# STB_ControlBoard.net
KiCad netlist of a schematic drawn in Altium Designer
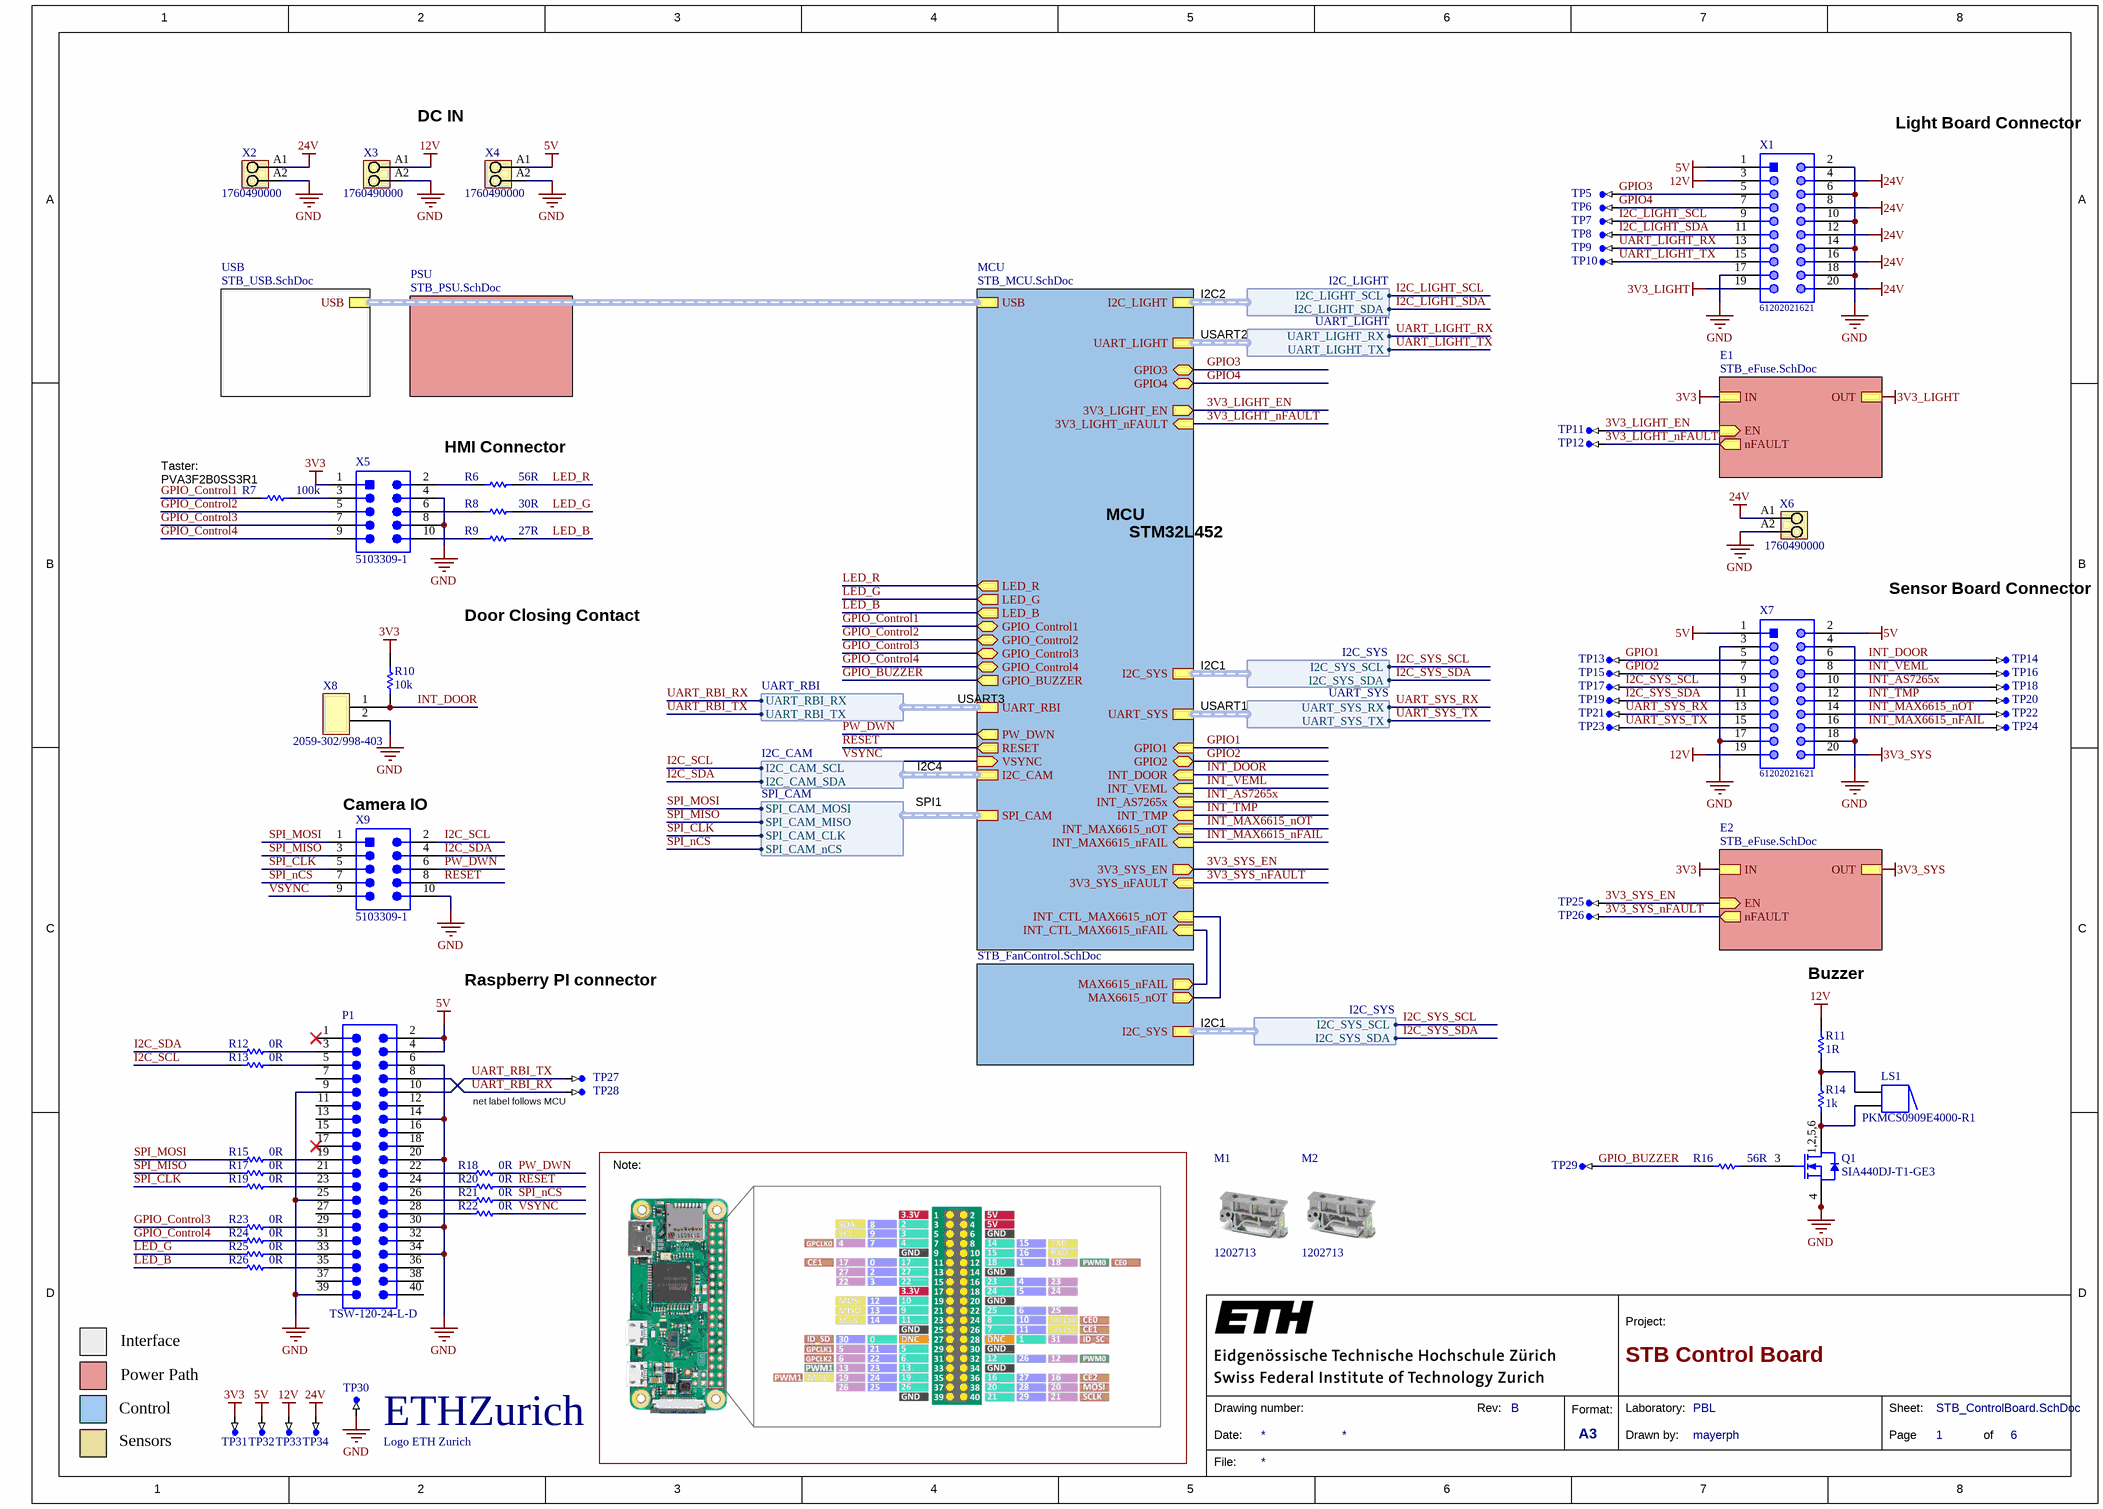
[diagram p0: STB_ControlBoard.SchDoc]

(export (version "E")
  (design (tool "Eeschema 10.0.6"))
  (components
    (comp (ref "A1")
      (value "Logo ETH Zurich")
      (footprint "eth-zurich_3mm")
      (libsource (lib "ETHZ Vault") (part "Logo ETH Zurich"))
    )
    (comp (ref "LS1")
      (value "PKMCS0909E4000-R1")
      (footprint "MURA- PKMCS0909E4000-2_V")
      (description "Audio Indicators & Alerts Piezo Buzzer, 12.5 V, -40 to 85 degC, 2-Pin SMD, RoHS, Tape and Reel")
      (fields (field (name "MANUFACTURER") "Murata"))
      (libsource (lib "Altium Content Vault") (part "MURA-PKMCS0909E4000-2"))
    )
    (comp (ref "M1")
      (value "1202713")
      (footprint "1202713")
      (description "EMI/EMD/EMC Protections")
      (fields (field (name "MANUFACTURER") "Phoenix Contact"))
      (libsource (lib "STB_Schlib") (part "1202713"))
    )
    (comp (ref "M2")
      (value "1202713")
      (footprint "1202713")
      (description "EMI/EMD/EMC Protections")
      (fields (field (name "MANUFACTURER") "Phoenix Contact"))
      (libsource (lib "STB_Schlib") (part "1202713"))
    )
    (comp (ref "P1")
      (value "TSW-120-24-L-D")
      (footprint "SMTC-TSW-120-24-X-D")
      (description "0.025\" SQ Post Header, Through-hole, Vertical, -55 to 125 degC, 2.54 mm Pitch, 40-Pin, Male, RoHS")
      (fields (field (name "MANUFACTURER") "Samtec"))
      (libsource (lib "Altium Content Vault") (part "SMTC-TSW-120-X-X-D-X"))
    )
    (comp (ref "Q1")
      (value "SIA440DJ-T1-GE3")
      (footprint "SC70-6L_65P210X80_HS-7L")
      (description "VISHAY   SIA440DJ-T1-GE3   MOSFET Transistor, N Channel, 12 A, 40 V, 0.021 ohm, 10 V")
      (fields (field (name "MANUFACTURER") "Vishay Siliconix"))
      (libsource (lib "STB_Schlib") (part "SIA440DJ-T1-GE3"))
    )
    (comp (ref "R6")
      (value "56R")
      (footprint "RESC1609X50X30LL10T20")
      (fields
        (field (name "MANUFACTURER") "Vishay Dale")
        (field (name "PART NUMBER") "CRCW060356R0FKEA")
        (field (name "TOLERANCE") "1%")
      )
      (libsource (lib "Altium Content Vault") (part "RES"))
    )
    (comp (ref "R7")
      (value "100k")
      (footprint "RESC1005X40X25LL05T10")
      (fields
        (field (name "PART NUMBER") "RC0402FR-07100KL")
        (field (name "MANUFACTURER") "Yageo / Phycomp")
        (field (name "TOLERANCE") "1%")
      )
      (libsource (lib "Altium Content Vault") (part "RES"))
    )
    (comp (ref "R8")
      (value "30R")
      (footprint "RESC1609X50X30LL10T20")
      (fields
        (field (name "PART NUMBER") "CRCW060330R0FKEA")
        (field (name "MANUFACTURER") "Vishay Dale")
        (field (name "TOLERANCE") "1%")
      )
      (libsource (lib "Altium Content Vault") (part "RES"))
    )
    (comp (ref "R9")
      (value "27R")
      (footprint "RESC1608X55X30LL15T15")
      (fields
        (field (name "PART NUMBER") "ERJ-3GEYJ270V")
        (field (name "MANUFACTURER") "Panasonic")
        (field (name "MANUFACTURER PART NUMBER") "ERJ-3EKF27R0V")
      )
      (libsource (lib "Altium Content Vault") (part "RES"))
    )
    (comp (ref "R10")
      (value "10k")
      (footprint "RESC1005X40X25LL05T05")
      (description "Chip Resistor, 10 KOhm, +/- 1%, 0.1 W, -55 to 155 degC, 0402 (1005 Metric), RoHS, Tape and Reel")
      (fields (field (name "TOLERANCE") "1%") (field (name "MANUFACTURER") "Panasonic"))
      (libsource (lib "Altium Content Vault") (part "RES-2"))
    )
    (comp (ref "R11")
      (value "1R")
      (footprint "RESC3225X70X50NL20T20")
      (fields
        (field (name "PART NUMBER") "ERJ14BQF1R0U")
        (field (name "MANUFACTURER") "Panasonic")
        (field (name "TOLERANCE") "1%")
      )
      (libsource (lib "Altium Content Vault") (part "RES"))
    )
    (comp (ref "R12")
      (value "0R")
      (footprint "RESC1005X40X25LL05T10")
      (fields (field (name "MANUFACTURER") "Yageo / Phycomp") (field (name "PART NUMBER") "RC0402JR-070RL"))
      (libsource (lib "Altium Content Vault") (part "RES"))
    )
    (comp (ref "R13")
      (value "0R")
      (footprint "RESC1005X40X25LL05T10")
      (fields (field (name "MANUFACTURER") "Yageo / Phycomp") (field (name "PART NUMBER") "RC0402JR-070RL"))
      (libsource (lib "Altium Content Vault") (part "RES"))
    )
    (comp (ref "R14")
      (value "1k")
      (footprint "RESC3216X70X50LL05T20")
      (fields
        (field (name "MANUFACTURER") "Panasonic")
        (field (name "PART NUMBER") "ERJ-8ENF1001V")
        (field (name "TOLERANCE") "1%")
      )
      (libsource (lib "Altium Content Vault") (part "RES"))
    )
    (comp (ref "R15")
      (value "0R")
      (footprint "RESC1005X40X25LL05T10")
      (fields (field (name "MANUFACTURER") "Yageo / Phycomp") (field (name "PART NUMBER") "RC0402JR-070RL"))
      (libsource (lib "Altium Content Vault") (part "RES"))
    )
    (comp (ref "R16")
      (value "56R")
      (footprint "RESC1609X50X30LL10T20")
      (fields
        (field (name "MANUFACTURER") "Vishay Dale")
        (field (name "PART NUMBER") "CRCW060356R0FKEA")
        (field (name "TOLERANCE") "1%")
      )
      (libsource (lib "Altium Content Vault") (part "RES"))
    )
    (comp (ref "R17")
      (value "0R")
      (footprint "RESC1005X40X25LL05T10")
      (fields (field (name "MANUFACTURER") "Yageo / Phycomp") (field (name "PART NUMBER") "RC0402JR-070RL"))
      (libsource (lib "Altium Content Vault") (part "RES"))
    )
    (comp (ref "R18")
      (value "0R")
      (footprint "RESC1005X40X25LL05T10")
      (fields (field (name "MANUFACTURER") "Yageo / Phycomp") (field (name "PART NUMBER") "RC0402JR-070RL"))
      (libsource (lib "Altium Content Vault") (part "RES"))
    )
    (comp (ref "R19")
      (value "0R")
      (footprint "RESC1005X40X25LL05T10")
      (fields (field (name "MANUFACTURER") "Yageo / Phycomp") (field (name "PART NUMBER") "RC0402JR-070RL"))
      (libsource (lib "Altium Content Vault") (part "RES"))
    )
    (comp (ref "R20")
      (value "0R")
      (footprint "RESC1005X40X25LL05T10")
      (fields (field (name "MANUFACTURER") "Yageo / Phycomp") (field (name "PART NUMBER") "RC0402JR-070RL"))
      (libsource (lib "Altium Content Vault") (part "RES"))
    )
    (comp (ref "R21")
      (value "0R")
      (footprint "RESC1005X40X25LL05T10")
      (fields (field (name "MANUFACTURER") "Yageo / Phycomp") (field (name "PART NUMBER") "RC0402JR-070RL"))
      (libsource (lib "Altium Content Vault") (part "RES"))
    )
    (comp (ref "R22")
      (value "0R")
      (footprint "RESC1005X40X25LL05T10")
      (fields (field (name "MANUFACTURER") "Yageo / Phycomp") (field (name "PART NUMBER") "RC0402JR-070RL"))
      (libsource (lib "Altium Content Vault") (part "RES"))
    )
    (comp (ref "R23")
      (value "0R")
      (footprint "RESC1005X40X25LL05T10")
      (fields (field (name "MANUFACTURER") "Yageo / Phycomp") (field (name "PART NUMBER") "RC0402JR-070RL"))
      (libsource (lib "Altium Content Vault") (part "RES"))
    )
    (comp (ref "R24")
      (value "0R")
      (footprint "RESC1005X40X25LL05T10")
      (fields (field (name "MANUFACTURER") "Yageo / Phycomp") (field (name "PART NUMBER") "RC0402JR-070RL"))
      (libsource (lib "Altium Content Vault") (part "RES"))
    )
    (comp (ref "R25")
      (value "0R")
      (footprint "RESC1005X40X25LL05T10")
      (fields (field (name "MANUFACTURER") "Yageo / Phycomp") (field (name "PART NUMBER") "RC0402JR-070RL"))
      (libsource (lib "Altium Content Vault") (part "RES"))
    )
    (comp (ref "R26")
      (value "0R")
      (footprint "RESC1005X40X25LL05T10")
      (fields (field (name "MANUFACTURER") "Yageo / Phycomp") (field (name "PART NUMBER") "RC0402JR-070RL"))
      (libsource (lib "Altium Content Vault") (part "RES"))
    )
    (comp (ref "TP5")
      (value "TP_1mm")
      (footprint "TP-SM-C-100")
      (description "testPoint 1mm")
      (libsource (lib "STB_Schlib") (part "testPoint_1mm"))
    )
    (comp (ref "TP6")
      (value "TP_1mm")
      (footprint "TP-SM-C-100")
      (description "testPoint 1mm")
      (libsource (lib "STB_Schlib") (part "testPoint_1mm"))
    )
    (comp (ref "TP7")
      (value "TP_1mm")
      (footprint "TP-SM-C-100")
      (description "testPoint 1mm")
      (libsource (lib "STB_Schlib") (part "testPoint_1mm"))
    )
    (comp (ref "TP8")
      (value "TP_1mm")
      (footprint "TP-SM-C-100")
      (description "testPoint 1mm")
      (libsource (lib "STB_Schlib") (part "testPoint_1mm"))
    )
    (comp (ref "TP9")
      (value "TP_1mm")
      (footprint "TP-SM-C-100")
      (description "testPoint 1mm")
      (libsource (lib "STB_Schlib") (part "testPoint_1mm"))
    )
    (comp (ref "TP10")
      (value "TP_1mm")
      (footprint "TP-SM-C-100")
      (description "testPoint 1mm")
      (libsource (lib "STB_Schlib") (part "testPoint_1mm"))
    )
    (comp (ref "TP11")
      (value "TP_1mm")
      (footprint "TP-SM-C-100")
      (description "testPoint 1mm")
      (libsource (lib "STB_Schlib") (part "testPoint_1mm"))
    )
    (comp (ref "TP12")
      (value "TP_1mm")
      (footprint "TP-SM-C-100")
      (description "testPoint 1mm")
      (libsource (lib "STB_Schlib") (part "testPoint_1mm"))
    )
    (comp (ref "TP13")
      (value "TP_1mm")
      (footprint "TP-SM-C-100")
      (description "testPoint 1mm")
      (libsource (lib "STB_Schlib") (part "testPoint_1mm"))
    )
    (comp (ref "TP14")
      (value "TP_1mm")
      (footprint "TP-SM-C-100")
      (description "testPoint 1mm")
      (libsource (lib "STB_Schlib") (part "testPoint_1mm"))
    )
    (comp (ref "TP15")
      (value "TP_1mm")
      (footprint "TP-SM-C-100")
      (description "testPoint 1mm")
      (libsource (lib "STB_Schlib") (part "testPoint_1mm"))
    )
    (comp (ref "TP16")
      (value "TP_1mm")
      (footprint "TP-SM-C-100")
      (description "testPoint 1mm")
      (libsource (lib "STB_Schlib") (part "testPoint_1mm"))
    )
    (comp (ref "TP17")
      (value "TP_1mm")
      (footprint "TP-SM-C-100")
      (description "testPoint 1mm")
      (libsource (lib "STB_Schlib") (part "testPoint_1mm"))
    )
    (comp (ref "TP18")
      (value "TP_1mm")
      (footprint "TP-SM-C-100")
      (description "testPoint 1mm")
      (libsource (lib "STB_Schlib") (part "testPoint_1mm"))
    )
    (comp (ref "TP19")
      (value "TP_1mm")
      (footprint "TP-SM-C-100")
      (description "testPoint 1mm")
      (libsource (lib "STB_Schlib") (part "testPoint_1mm"))
    )
    (comp (ref "TP20")
      (value "TP_1mm")
      (footprint "TP-SM-C-100")
      (description "testPoint 1mm")
      (libsource (lib "STB_Schlib") (part "testPoint_1mm"))
    )
    (comp (ref "TP21")
      (value "TP_1mm")
      (footprint "TP-SM-C-100")
      (description "testPoint 1mm")
      (libsource (lib "STB_Schlib") (part "testPoint_1mm"))
    )
    (comp (ref "TP22")
      (value "TP_1mm")
      (footprint "TP-SM-C-100")
      (description "testPoint 1mm")
      (libsource (lib "STB_Schlib") (part "testPoint_1mm"))
    )
    (comp (ref "TP23")
      (value "TP_1mm")
      (footprint "TP-SM-C-100")
      (description "testPoint 1mm")
      (libsource (lib "STB_Schlib") (part "testPoint_1mm"))
    )
    (comp (ref "TP24")
      (value "TP_1mm")
      (footprint "TP-SM-C-100")
      (description "testPoint 1mm")
      (libsource (lib "STB_Schlib") (part "testPoint_1mm"))
    )
    (comp (ref "TP25")
      (value "TP_1mm")
      (footprint "TP-SM-C-100")
      (description "testPoint 1mm")
      (libsource (lib "STB_Schlib") (part "testPoint_1mm"))
    )
    (comp (ref "TP26")
      (value "TP_1mm")
      (footprint "TP-SM-C-100")
      (description "testPoint 1mm")
      (libsource (lib "STB_Schlib") (part "testPoint_1mm"))
    )
    (comp (ref "TP27")
      (value "TP_1mm")
      (footprint "TP-SM-C-100")
      (description "testPoint 1mm")
      (libsource (lib "STB_Schlib") (part "testPoint_1mm"))
    )
    (comp (ref "TP28")
      (value "TP_1mm")
      (footprint "TP-SM-C-100")
      (description "testPoint 1mm")
      (libsource (lib "STB_Schlib") (part "testPoint_1mm"))
    )
    (comp (ref "TP29")
      (value "TP_1mm")
      (footprint "TP-SM-C-100")
      (description "testPoint 1mm")
      (libsource (lib "STB_Schlib") (part "testPoint_1mm"))
    )
    (comp (ref "TP30")
      (value "TP_1mm")
      (footprint "TP-SM-C-100")
      (description "testPoint 1mm")
      (libsource (lib "STB_Schlib") (part "testPoint_1mm"))
    )
    (comp (ref "TP31")
      (value "TP_1mm")
      (footprint "TP-SM-C-100")
      (description "testPoint 1mm")
      (libsource (lib "STB_Schlib") (part "testPoint_1mm"))
    )
    (comp (ref "TP32")
      (value "TP_1mm")
      (footprint "TP-SM-C-100")
      (description "testPoint 1mm")
      (libsource (lib "STB_Schlib") (part "testPoint_1mm"))
    )
    (comp (ref "TP33")
      (value "TP_1mm")
      (footprint "TP-SM-C-100")
      (description "testPoint 1mm")
      (libsource (lib "STB_Schlib") (part "testPoint_1mm"))
    )
    (comp (ref "TP34")
      (value "TP_1mm")
      (footprint "TP-SM-C-100")
      (description "testPoint 1mm")
      (libsource (lib "STB_Schlib") (part "testPoint_1mm"))
    )
    (comp (ref "X1")
      (value "61202021621")
      (footprint "61202021621")
      (description "Male Box Header WR-BHD, THT, Vertical, pitch 2.54 mm, 20 pins")
      (fields (field (name "MANUFACTURER") "Wurth Elektronik") (field (name "PUBLISHER") "WurthElektronik"))
      (libsource (lib "Altium Content Vault") (part "WE-CN-2P-M-R20"))
    )
    (comp (ref "X2")
      (value "1760490000")
      (footprint "PM_5_08_90_02")
      (description "OMNIMATE Signal - series PM")
      (fields (field (name "MANUFACTURER") "Weidmueller") (field (name "SAFETY APPROVAL") "UL,CSA"))
      (libsource (lib "Altium Content Vault") (part "Terminal_02_1x02"))
    )
    (comp (ref "X3")
      (value "1760490000")
      (footprint "PM_5_08_90_02")
      (description "OMNIMATE Signal - series PM")
      (fields (field (name "MANUFACTURER") "Weidmueller") (field (name "SAFETY APPROVAL") "UL,CSA"))
      (libsource (lib "Altium Content Vault") (part "Terminal_02_1x02"))
    )
    (comp (ref "X4")
      (value "1760490000")
      (footprint "PM_5_08_90_02")
      (description "OMNIMATE Signal - series PM")
      (fields (field (name "MANUFACTURER") "Weidmueller") (field (name "SAFETY APPROVAL") "UL,CSA"))
      (libsource (lib "Altium Content Vault") (part "Terminal_02_1x02"))
    )
    (comp (ref "X5")
      (value "5103309-1")
      (footprint "TECO-5103309-1_V")
      (fields (field (name "MANUFACTURER") "TE Connectivity"))
      (libsource (lib "Altium Content Vault") (part "CN-2P-M-R10"))
    )
    (comp (ref "X6")
      (value "1760490000")
      (footprint "PM_5_08_90_02")
      (description "OMNIMATE Signal - series PM")
      (fields (field (name "MANUFACTURER") "Weidmueller") (field (name "SAFETY APPROVAL") "UL,CSA"))
      (libsource (lib "") (part "Terminal_02_1x02_1"))
    )
    (comp (ref "X7")
      (value "61202021621")
      (footprint "61202021621")
      (description "Male Box Header WR-BHD, THT, Vertical, pitch 2.54 mm, 20 pins")
      (fields (field (name "MANUFACTURER") "Wurth Elektronik") (field (name "PUBLISHER") "WurthElektronik"))
      (libsource (lib "Altium Content Vault") (part "WE-CN-2P-M-R20"))
    )
    (comp (ref "X8")
      (value "2059-302/998-403")
      (footprint "2059-302/998-403")
      (description "Barrier Strip Terminal Block, 3A, 0.34mm2, 1 Row(s), 1 Deck(s)")
      (fields (field (name "MANUFACTURER") "WAGO") (field (name "SAFETY APPROVAL") "UL"))
      (libsource (lib "STB_Schlib") (part "2059-302/998-403"))
    )
    (comp (ref "X9")
      (value "5103309-1")
      (footprint "TECO-5103309-1_V")
      (fields (field (name "MANUFACTURER") "TE Connectivity"))
      (libsource (lib "Altium Content Vault") (part "CN-2P-M-R10"))
    )
  )
  (nets
    (net (code "8") (name "/3V3_LIGHT_EN") (class "Default")
      (node (ref "TP11") (pin "TP") (pinfunction "TP_TP") (pintype "input"))
    )
    (net (code "9") (name "/3V3_LIGHT_nFAULT") (class "Default")
      (node (ref "TP12") (pin "TP") (pinfunction "TP_TP") (pintype "input"))
    )
    (net (code "10") (name "/3V3_SYS_EN") (class "Default")
      (node (ref "TP25") (pin "TP") (pinfunction "TP_TP") (pintype "input"))
    )
    (net (code "11") (name "/3V3_SYS_nFAULT") (class "Default")
      (node (ref "TP26") (pin "TP") (pinfunction "TP_TP") (pintype "input"))
    )
    (net (code "12") (name "/GPIO1") (class "Default")
      (node (ref "TP13") (pin "TP") (pinfunction "TP_TP") (pintype "input"))
      (node (ref "X7") (pin "5") (pinfunction "5_5") (pintype "passive"))
    )
    (net (code "13") (name "/GPIO2") (class "Default")
      (node (ref "TP15") (pin "TP") (pinfunction "TP_TP") (pintype "input"))
      (node (ref "X7") (pin "7") (pinfunction "7_7") (pintype "passive"))
    )
    (net (code "14") (name "/GPIO3") (class "Default")
      (node (ref "TP5") (pin "TP") (pinfunction "TP_TP") (pintype "input"))
      (node (ref "X1") (pin "5") (pinfunction "5_5") (pintype "passive"))
    )
    (net (code "15") (name "/GPIO4") (class "Default")
      (node (ref "TP6") (pin "TP") (pinfunction "TP_TP") (pintype "input"))
      (node (ref "X1") (pin "7") (pinfunction "7_7") (pintype "passive"))
    )
    (net (code "16") (name "/GPIO_BUZZER") (class "Default")
      (node (ref "R16") (pin "2") (pinfunction "2_2") (pintype "passive"))
      (node (ref "TP29") (pin "TP") (pinfunction "TP_TP") (pintype "input"))
    )
    (net (code "17") (name "/GPIO_Control1") (class "Default")
      (node (ref "R7") (pin "2") (pinfunction "2_2") (pintype "passive"))
    )
    (net (code "18") (name "/GPIO_Control2") (class "Default")
      (node (ref "X5") (pin "5") (pinfunction "5_5") (pintype "passive"))
    )
    (net (code "19") (name "/GPIO_Control3") (class "Default")
      (node (ref "R23") (pin "1") (pinfunction "1_1") (pintype "passive"))
      (node (ref "X5") (pin "7") (pinfunction "7_7") (pintype "passive"))
    )
    (net (code "20") (name "/GPIO_Control4") (class "Default")
      (node (ref "R24") (pin "1") (pinfunction "1_1") (pintype "passive"))
      (node (ref "X5") (pin "9") (pinfunction "9_9") (pintype "passive"))
    )
    (net (code "21") (name "/I2C_LIGHT_SCL") (class "Default")
      (node (ref "TP7") (pin "TP") (pinfunction "TP_TP") (pintype "input"))
      (node (ref "X1") (pin "9") (pinfunction "9_9") (pintype "passive"))
    )
    (net (code "22") (name "/I2C_LIGHT_SDA") (class "Default")
      (node (ref "TP8") (pin "TP") (pinfunction "TP_TP") (pintype "input"))
      (node (ref "X1") (pin "11") (pinfunction "11_11") (pintype "passive"))
    )
    (net (code "23") (name "/I2C_SCL") (class "Default")
      (node (ref "R13") (pin "1") (pinfunction "1_1") (pintype "passive"))
      (node (ref "X9") (pin "2") (pinfunction "2_2") (pintype "passive"))
    )
    (net (code "24") (name "/I2C_SDA") (class "Default")
      (node (ref "R12") (pin "1") (pinfunction "1_1") (pintype "passive"))
      (node (ref "X9") (pin "4") (pinfunction "4_4") (pintype "passive"))
    )
    (net (code "25") (name "/I2C_SYS_SCL") (class "Default")
      (node (ref "TP17") (pin "TP") (pinfunction "TP_TP") (pintype "input"))
      (node (ref "X7") (pin "9") (pinfunction "9_9") (pintype "passive"))
    )
    (net (code "26") (name "/I2C_SYS_SDA") (class "Default")
      (node (ref "TP19") (pin "TP") (pinfunction "TP_TP") (pintype "input"))
      (node (ref "X7") (pin "11") (pinfunction "11_11") (pintype "passive"))
    )
    (net (code "27") (name "/INT_AS7265x") (class "Default")
      (node (ref "TP18") (pin "TP") (pinfunction "TP_TP") (pintype "input"))
      (node (ref "X7") (pin "10") (pinfunction "10_10") (pintype "passive"))
    )
    (net (code "28") (name "/INT_DOOR") (class "Default")
      (node (ref "R10") (pin "1") (pinfunction "1_1") (pintype "passive"))
      (node (ref "TP14") (pin "TP") (pinfunction "TP_TP") (pintype "input"))
      (node (ref "X7") (pin "6") (pinfunction "6_6") (pintype "passive"))
      (node (ref "X8") (pin "1") (pintype "passive"))
    )
    (net (code "29") (name "/INT_MAX6615_nFAIL") (class "Default")
      (node (ref "TP24") (pin "TP") (pinfunction "TP_TP") (pintype "input"))
      (node (ref "X7") (pin "16") (pinfunction "16_16") (pintype "passive"))
    )
    (net (code "30") (name "/INT_MAX6615_nOT") (class "Default")
      (node (ref "TP22") (pin "TP") (pinfunction "TP_TP") (pintype "input"))
      (node (ref "X7") (pin "14") (pinfunction "14_14") (pintype "passive"))
    )
    (net (code "31") (name "/INT_TMP") (class "Default")
      (node (ref "TP20") (pin "TP") (pinfunction "TP_TP") (pintype "input"))
      (node (ref "X7") (pin "12") (pinfunction "12_12") (pintype "passive"))
    )
    (net (code "32") (name "/INT_VEML") (class "Default")
      (node (ref "TP16") (pin "TP") (pinfunction "TP_TP") (pintype "input"))
      (node (ref "X7") (pin "8") (pinfunction "8_8") (pintype "passive"))
    )
    (net (code "33") (name "/LED_B") (class "Default")
      (node (ref "R26") (pin "1") (pinfunction "1_1") (pintype "passive"))
      (node (ref "R9") (pin "1") (pinfunction "1_1") (pintype "passive"))
    )
    (net (code "34") (name "/LED_G") (class "Default")
      (node (ref "R25") (pin "1") (pinfunction "1_1") (pintype "passive"))
      (node (ref "R8") (pin "1") (pinfunction "1_1") (pintype "passive"))
    )
    (net (code "35") (name "/LED_R") (class "Default")
      (node (ref "R6") (pin "1") (pinfunction "1_1") (pintype "passive"))
    )
    (net (code "38") (name "/PW_DWN") (class "Default")
      (node (ref "R18") (pin "2") (pinfunction "2_2") (pintype "passive"))
      (node (ref "X9") (pin "6") (pinfunction "6_6") (pintype "passive"))
    )
    (net (code "39") (name "/RESET") (class "Default")
      (node (ref "R20") (pin "2") (pinfunction "2_2") (pintype "passive"))
      (node (ref "X9") (pin "8") (pinfunction "8_8") (pintype "passive"))
    )
    (net (code "40") (name "/SPI_CLK") (class "Default")
      (node (ref "R19") (pin "1") (pinfunction "1_1") (pintype "passive"))
      (node (ref "X9") (pin "5") (pinfunction "5_5") (pintype "passive"))
    )
    (net (code "41") (name "/SPI_MISO") (class "Default")
      (node (ref "R17") (pin "1") (pinfunction "1_1") (pintype "passive"))
      (node (ref "X9") (pin "3") (pinfunction "3_3") (pintype "passive"))
    )
    (net (code "42") (name "/SPI_MOSI") (class "Default")
      (node (ref "R15") (pin "1") (pinfunction "1_1") (pintype "passive"))
      (node (ref "X9") (pin "1") (pinfunction "1_1") (pintype "passive"))
    )
    (net (code "43") (name "/SPI_nCS") (class "Default")
      (node (ref "R21") (pin "2") (pinfunction "2_2") (pintype "passive"))
      (node (ref "X9") (pin "7") (pinfunction "7_7") (pintype "passive"))
    )
    (net (code "44") (name "/UART_LIGHT_RX") (class "Default")
      (node (ref "TP9") (pin "TP") (pinfunction "TP_TP") (pintype "input"))
      (node (ref "X1") (pin "13") (pinfunction "13_13") (pintype "passive"))
    )
    (net (code "45") (name "/UART_LIGHT_TX") (class "Default")
      (node (ref "TP10") (pin "TP") (pinfunction "TP_TP") (pintype "input"))
      (node (ref "X1") (pin "15") (pinfunction "15_15") (pintype "passive"))
    )
    (net (code "46") (name "/UART_RBI_RX") (class "Default")
      (node (ref "P1") (pin "8") (pinfunction "8_8") (pintype "passive"))
      (node (ref "TP28") (pin "TP") (pinfunction "TP_TP") (pintype "input"))
    )
    (net (code "47") (name "/UART_RBI_TX") (class "Default")
      (node (ref "P1") (pin "10") (pinfunction "10_10") (pintype "passive"))
      (node (ref "TP27") (pin "TP") (pinfunction "TP_TP") (pintype "input"))
    )
    (net (code "48") (name "/UART_SYS_RX") (class "Default")
      (node (ref "TP21") (pin "TP") (pinfunction "TP_TP") (pintype "input"))
      (node (ref "X7") (pin "13") (pinfunction "13_13") (pintype "passive"))
    )
    (net (code "49") (name "/UART_SYS_TX") (class "Default")
      (node (ref "TP23") (pin "TP") (pinfunction "TP_TP") (pintype "input"))
      (node (ref "X7") (pin "15") (pinfunction "15_15") (pintype "passive"))
    )
    (net (code "51") (name "/VSYNC") (class "Default")
      (node (ref "R22") (pin "2") (pinfunction "2_2") (pintype "passive"))
      (node (ref "X9") (pin "9") (pinfunction "9_9") (pintype "passive"))
    )
    (net (code "59") (name "3V3") (class "Default")
      (node (ref "R10") (pin "2") (pinfunction "2_2") (pintype "passive"))
      (node (ref "TP31") (pin "TP") (pinfunction "TP_TP") (pintype "input"))
      (node (ref "X5") (pin "1") (pinfunction "1_1") (pintype "passive"))
    )
    (net (code "60") (name "3V3_LIGHT") (class "Default")
      (node (ref "X1") (pin "19") (pinfunction "19_19") (pintype "passive"))
    )
    (net (code "61") (name "3V3_SYS") (class "Default")
      (node (ref "X7") (pin "20") (pinfunction "20_20") (pintype "passive"))
    )
    (net (code "62") (name "5V") (class "Default")
      (node (ref "P1") (pin "2") (pinfunction "2_2") (pintype "passive"))
      (node (ref "P1") (pin "4") (pinfunction "4_4") (pintype "passive"))
      (node (ref "TP32") (pin "TP") (pinfunction "TP_TP") (pintype "input"))
      (node (ref "X1") (pin "1") (pinfunction "1_1") (pintype "passive"))
      (node (ref "X4") (pin "A1") (pinfunction "A1_A1") (pintype "passive"))
      (node (ref "X7") (pin "1") (pinfunction "1_1") (pintype "passive"))
      (node (ref "X7") (pin "2") (pinfunction "2_2") (pintype "passive"))
    )
    (net (code "63") (name "12V") (class "Default")
      (node (ref "R11") (pin "2") (pinfunction "2_2") (pintype "passive"))
      (node (ref "TP33") (pin "TP") (pinfunction "TP_TP") (pintype "input"))
      (node (ref "X1") (pin "3") (pinfunction "3_3") (pintype "passive"))
      (node (ref "X3") (pin "A1") (pinfunction "A1_A1") (pintype "passive"))
      (node (ref "X7") (pin "19") (pinfunction "19_19") (pintype "passive"))
    )
    (net (code "64") (name "24V") (class "Default")
      (node (ref "TP34") (pin "TP") (pinfunction "TP_TP") (pintype "input"))
      (node (ref "X1") (pin "12") (pinfunction "12_12") (pintype "passive"))
      (node (ref "X1") (pin "16") (pinfunction "16_16") (pintype "passive"))
      (node (ref "X1") (pin "20") (pinfunction "20_20") (pintype "passive"))
      (node (ref "X1") (pin "4") (pinfunction "4_4") (pintype "passive"))
      (node (ref "X1") (pin "8") (pinfunction "8_8") (pintype "passive"))
      (node (ref "X2") (pin "A1") (pinfunction "A1_A1") (pintype "passive"))
      (node (ref "X6") (pin "A1") (pinfunction "A1_A1") (pintype "passive"))
    )
    (net (code "65") (name "GND") (class "Default")
      (node (ref "P1") (pin "14") (pinfunction "14_14") (pintype "passive"))
      (node (ref "P1") (pin "20") (pinfunction "20_20") (pintype "passive"))
      (node (ref "P1") (pin "25") (pinfunction "25_25") (pintype "passive"))
      (node (ref "P1") (pin "30") (pinfunction "30_30") (pintype "passive"))
      (node (ref "P1") (pin "34") (pinfunction "34_34") (pintype "passive"))
      (node (ref "P1") (pin "39") (pinfunction "39_39") (pintype "passive"))
      (node (ref "P1") (pin "6") (pinfunction "6_6") (pintype "passive"))
      (node (ref "P1") (pin "9") (pinfunction "9_9") (pintype "passive"))
      (node (ref "Q1") (pin "4") (pinfunction "SOURCE_4") (pintype "passive"))
      (node (ref "Q1") (pin "S") (pinfunction "SOURCE_S") (pintype "passive"))
      (node (ref "TP30") (pin "TP") (pinfunction "TP_TP") (pintype "input"))
      (node (ref "X1") (pin "10") (pinfunction "10_10") (pintype "passive"))
      (node (ref "X1") (pin "14") (pinfunction "14_14") (pintype "passive"))
      (node (ref "X1") (pin "17") (pinfunction "17_17") (pintype "passive"))
      (node (ref "X1") (pin "18") (pinfunction "18_18") (pintype "passive"))
      (node (ref "X1") (pin "2") (pinfunction "2_2") (pintype "passive"))
      (node (ref "X1") (pin "6") (pinfunction "6_6") (pintype "passive"))
      (node (ref "X2") (pin "A2") (pinfunction "A2_A2") (pintype "passive"))
      (node (ref "X3") (pin "A2") (pinfunction "A2_A2") (pintype "passive"))
      (node (ref "X4") (pin "A2") (pinfunction "A2_A2") (pintype "passive"))
      (node (ref "X5") (pin "4") (pinfunction "4_4") (pintype "passive"))
      (node (ref "X5") (pin "8") (pinfunction "8_8") (pintype "passive"))
      (node (ref "X6") (pin "A2") (pinfunction "A2_A2") (pintype "passive"))
      (node (ref "X7") (pin "17") (pinfunction "17_17") (pintype "passive"))
      (node (ref "X7") (pin "18") (pinfunction "18_18") (pintype "passive"))
      (node (ref "X7") (pin "3") (pinfunction "3_3") (pintype "passive"))
      (node (ref "X7") (pin "4") (pinfunction "4_4") (pintype "passive"))
      (node (ref "X8") (pin "2") (pintype "passive"))
      (node (ref "X9") (pin "10") (pinfunction "10_10") (pintype "passive"))
    )
    (net (code "66") (name "Net-(LS1-Pad1)") (class "Default")
      (node (ref "LS1") (pin "1") (pinfunction "1_1") (pintype "passive"))
      (node (ref "R11") (pin "1") (pinfunction "1_1") (pintype "passive"))
      (node (ref "R14") (pin "2") (pinfunction "2_2") (pintype "passive"))
    )
    (net (code "67") (name "Net-(LS1-Pad2)") (class "Default")
      (node (ref "LS1") (pin "2") (pinfunction "2_2") (pintype "passive"))
      (node (ref "Q1") (pin "1") (pinfunction "DRAIN_1") (pintype "passive"))
      (node (ref "Q1") (pin "2") (pinfunction "DRAIN_2") (pintype "passive"))
      (node (ref "Q1") (pin "5") (pinfunction "DRAIN_5") (pintype "passive"))
      (node (ref "Q1") (pin "6") (pinfunction "DRAIN_6") (pintype "passive"))
      (node (ref "Q1") (pin "TP") (pinfunction "DRAIN_TP") (pintype "passive"))
      (node (ref "R14") (pin "1") (pinfunction "1_1") (pintype "passive"))
    )
    (net (code "68") (name "Net-(P1-Pad3)") (class "Default")
      (node (ref "P1") (pin "3") (pinfunction "3_3") (pintype "passive"))
      (node (ref "R12") (pin "2") (pinfunction "2_2") (pintype "passive"))
    )
    (net (code "69") (name "Net-(P1-Pad5)") (class "Default")
      (node (ref "P1") (pin "5") (pinfunction "5_5") (pintype "passive"))
      (node (ref "R13") (pin "2") (pinfunction "2_2") (pintype "passive"))
    )
    (net (code "70") (name "Net-(P1-Pad19)") (class "Default")
      (node (ref "P1") (pin "19") (pinfunction "19_19") (pintype "passive"))
      (node (ref "R15") (pin "2") (pinfunction "2_2") (pintype "passive"))
    )
    (net (code "71") (name "Net-(P1-Pad21)") (class "Default")
      (node (ref "P1") (pin "21") (pinfunction "21_21") (pintype "passive"))
      (node (ref "R17") (pin "2") (pinfunction "2_2") (pintype "passive"))
    )
    (net (code "72") (name "Net-(P1-Pad22)") (class "Default")
      (node (ref "P1") (pin "22") (pinfunction "22_22") (pintype "passive"))
      (node (ref "R18") (pin "1") (pinfunction "1_1") (pintype "passive"))
    )
    (net (code "73") (name "Net-(P1-Pad23)") (class "Default")
      (node (ref "P1") (pin "23") (pinfunction "23_23") (pintype "passive"))
      (node (ref "R19") (pin "2") (pinfunction "2_2") (pintype "passive"))
    )
    (net (code "74") (name "Net-(P1-Pad24)") (class "Default")
      (node (ref "P1") (pin "24") (pinfunction "24_24") (pintype "passive"))
      (node (ref "R20") (pin "1") (pinfunction "1_1") (pintype "passive"))
    )
    (net (code "75") (name "Net-(P1-Pad26)") (class "Default")
      (node (ref "P1") (pin "26") (pinfunction "26_26") (pintype "passive"))
      (node (ref "R21") (pin "1") (pinfunction "1_1") (pintype "passive"))
    )
    (net (code "76") (name "Net-(P1-Pad28)") (class "Default")
      (node (ref "P1") (pin "28") (pinfunction "28_28") (pintype "passive"))
      (node (ref "R22") (pin "1") (pinfunction "1_1") (pintype "passive"))
    )
    (net (code "77") (name "Net-(P1-Pad29)") (class "Default")
      (node (ref "P1") (pin "29") (pinfunction "29_29") (pintype "passive"))
      (node (ref "R23") (pin "2") (pinfunction "2_2") (pintype "passive"))
    )
    (net (code "78") (name "Net-(P1-Pad31)") (class "Default")
      (node (ref "P1") (pin "31") (pinfunction "31_31") (pintype "passive"))
      (node (ref "R24") (pin "2") (pinfunction "2_2") (pintype "passive"))
    )
    (net (code "79") (name "Net-(P1-Pad33)") (class "Default")
      (node (ref "P1") (pin "33") (pinfunction "33_33") (pintype "passive"))
      (node (ref "R25") (pin "2") (pinfunction "2_2") (pintype "passive"))
    )
    (net (code "80") (name "Net-(P1-Pad35)") (class "Default")
      (node (ref "P1") (pin "35") (pinfunction "35_35") (pintype "passive"))
      (node (ref "R26") (pin "2") (pinfunction "2_2") (pintype "passive"))
    )
    (net (code "81") (name "Net-(Q1-GATE)") (class "Default")
      (node (ref "Q1") (pin "3") (pinfunction "GATE_3") (pintype "passive"))
      (node (ref "R16") (pin "1") (pinfunction "1_1") (pintype "passive"))
    )
    (net (code "82") (name "Net-(R6-Pad2)") (class "Default")
      (node (ref "R6") (pin "2") (pinfunction "2_2") (pintype "passive"))
      (node (ref "X5") (pin "2") (pinfunction "2_2") (pintype "passive"))
    )
    (net (code "83") (name "Net-(R7-Pad1)") (class "Default")
      (node (ref "R7") (pin "1") (pinfunction "1_1") (pintype "passive"))
      (node (ref "X5") (pin "3") (pinfunction "3_3") (pintype "passive"))
    )
    (net (code "84") (name "Net-(R8-Pad2)") (class "Default")
      (node (ref "R8") (pin "2") (pinfunction "2_2") (pintype "passive"))
      (node (ref "X5") (pin "6") (pinfunction "6_6") (pintype "passive"))
    )
    (net (code "85") (name "Net-(R9-Pad2)") (class "Default")
      (node (ref "R9") (pin "2") (pinfunction "2_2") (pintype "passive"))
      (node (ref "X5") (pin "10") (pinfunction "10_10") (pintype "passive"))
    )
    (net (code "86") (name "unconnected-(P1-Pad1)") (class "Default")
      (node (ref "P1") (pin "1") (pinfunction "1_1") (pintype "passive+no_connect"))
    )
    (net (code "87") (name "unconnected-(P1-Pad7)") (class "Default")
      (node (ref "P1") (pin "7") (pinfunction "7_7") (pintype "passive"))
    )
    (net (code "88") (name "unconnected-(P1-Pad11)") (class "Default")
      (node (ref "P1") (pin "11") (pinfunction "11_11") (pintype "passive"))
    )
    (net (code "89") (name "unconnected-(P1-Pad12)") (class "Default")
      (node (ref "P1") (pin "12") (pinfunction "12_12") (pintype "passive"))
    )
    (net (code "90") (name "unconnected-(P1-Pad13)") (class "Default")
      (node (ref "P1") (pin "13") (pinfunction "13_13") (pintype "passive"))
    )
    (net (code "91") (name "unconnected-(P1-Pad15)") (class "Default")
      (node (ref "P1") (pin "15") (pinfunction "15_15") (pintype "passive"))
    )
    (net (code "92") (name "unconnected-(P1-Pad16)") (class "Default")
      (node (ref "P1") (pin "16") (pinfunction "16_16") (pintype "passive"))
    )
    (net (code "93") (name "unconnected-(P1-Pad17)") (class "Default")
      (node (ref "P1") (pin "17") (pinfunction "17_17") (pintype "passive+no_connect"))
    )
    (net (code "94") (name "unconnected-(P1-Pad18)") (class "Default")
      (node (ref "P1") (pin "18") (pinfunction "18_18") (pintype "passive"))
    )
    (net (code "95") (name "unconnected-(P1-Pad27)") (class "Default")
      (node (ref "P1") (pin "27") (pinfunction "27_27") (pintype "passive"))
    )
    (net (code "96") (name "unconnected-(P1-Pad32)") (class "Default")
      (node (ref "P1") (pin "32") (pinfunction "32_32") (pintype "passive"))
    )
    (net (code "97") (name "unconnected-(P1-Pad36)") (class "Default")
      (node (ref "P1") (pin "36") (pinfunction "36_36") (pintype "passive"))
    )
    (net (code "98") (name "unconnected-(P1-Pad37)") (class "Default")
      (node (ref "P1") (pin "37") (pinfunction "37_37") (pintype "passive"))
    )
    (net (code "99") (name "unconnected-(P1-Pad38)") (class "Default")
      (node (ref "P1") (pin "38") (pinfunction "38_38") (pintype "passive"))
    )
    (net (code "100") (name "unconnected-(P1-Pad40)") (class "Default")
      (node (ref "P1") (pin "40") (pinfunction "40_40") (pintype "passive"))
    )
  )
)
